# PCB.net
KiCad netlist of a schematic drawn in EAGLE
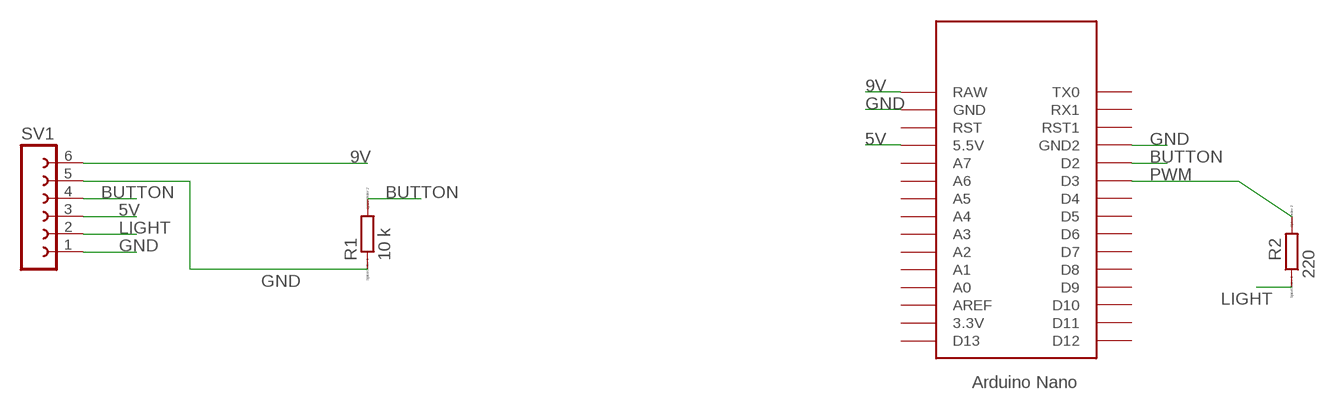
[diagram p0: schematic, sheet 1]

(export (version "E")
  (design (tool "Eeschema 10.0.6"))
  (components
    (comp (ref "R1")
      (value "10 k")
      (footprint "eagle-import:R0805")
      (libsource (lib "eagle-import") (part "R"))
    )
    (comp (ref "R2")
      (value "220")
      (footprint "eagle-import:R0805")
      (libsource (lib "eagle-import") (part "R"))
    )
    (comp (ref "SV1")
      (value "FE06-1")
      (footprint "eagle-import:FE06")
      (libsource (lib "eagle-import") (part "FE06-1"))
    )
    (comp (ref "U$1")
      (value "NANO")
      (footprint "eagle-import:NANO")
      (libsource (lib "eagle-import") (part "NANO"))
    )
  )
  (nets
    (net (code "1") (name "/5V") (class "Default")
      (node (ref "SV1") (pin "3") (pinfunction "3_3") (pintype "passive"))
      (node (ref "U$1") (pin "5V") (pinfunction "5.5V_5V") (pintype "bidirectional"))
    )
    (net (code "2") (name "/9V") (class "Default")
      (node (ref "SV1") (pin "6") (pinfunction "6_6") (pintype "passive"))
      (node (ref "U$1") (pin "RAW") (pinfunction "RAW_RAW") (pintype "bidirectional"))
    )
    (net (code "3") (name "/BUTTON") (class "Default")
      (node (ref "R1") (pin "2") (pinfunction "2_2") (pintype "passive"))
      (node (ref "SV1") (pin "4") (pinfunction "4_4") (pintype "passive"))
      (node (ref "U$1") (pin "D2") (pinfunction "D2_D2") (pintype "bidirectional"))
    )
    (net (code "4") (name "/GND") (class "Default")
      (node (ref "R1") (pin "1") (pinfunction "1_1") (pintype "passive"))
      (node (ref "SV1") (pin "1") (pinfunction "1_1") (pintype "passive"))
      (node (ref "SV1") (pin "5") (pinfunction "5_5") (pintype "passive"))
      (node (ref "U$1") (pin "GND") (pinfunction "GND_GND") (pintype "bidirectional"))
      (node (ref "U$1") (pin "GND1") (pinfunction "GND2_GND1") (pintype "bidirectional"))
    )
    (net (code "5") (name "/LIGHT") (class "Default")
      (node (ref "R2") (pin "1") (pinfunction "1_1") (pintype "passive"))
      (node (ref "SV1") (pin "2") (pinfunction "2_2") (pintype "passive"))
    )
    (net (code "6") (name "/PWM") (class "Default")
      (node (ref "R2") (pin "2") (pinfunction "2_2") (pintype "passive"))
      (node (ref "U$1") (pin "D3") (pinfunction "D3_D3") (pintype "bidirectional"))
    )
    (net (code "7") (name "unconnected-(U$1-Pad3.3V)") (class "Default")
      (node (ref "U$1") (pin "3.3V") (pinfunction "3.3V_3.3V") (pintype "bidirectional"))
    )
    (net (code "8") (name "unconnected-(U$1-PadA0)") (class "Default")
      (node (ref "U$1") (pin "A0") (pinfunction "A0_A0") (pintype "bidirectional"))
    )
    (net (code "9") (name "unconnected-(U$1-PadA1)") (class "Default")
      (node (ref "U$1") (pin "A1") (pinfunction "A1_A1") (pintype "bidirectional"))
    )
    (net (code "10") (name "unconnected-(U$1-PadA2)") (class "Default")
      (node (ref "U$1") (pin "A2") (pinfunction "A2_A2") (pintype "bidirectional"))
    )
    (net (code "11") (name "unconnected-(U$1-PadA3)") (class "Default")
      (node (ref "U$1") (pin "A3") (pinfunction "A3_A3") (pintype "bidirectional"))
    )
    (net (code "12") (name "unconnected-(U$1-PadA4)") (class "Default")
      (node (ref "U$1") (pin "A4") (pinfunction "A4_A4") (pintype "bidirectional"))
    )
    (net (code "13") (name "unconnected-(U$1-PadA5)") (class "Default")
      (node (ref "U$1") (pin "A5") (pinfunction "A5_A5") (pintype "bidirectional"))
    )
    (net (code "14") (name "unconnected-(U$1-PadA6)") (class "Default")
      (node (ref "U$1") (pin "A6") (pinfunction "A6_A6") (pintype "bidirectional"))
    )
    (net (code "15") (name "unconnected-(U$1-PadA7)") (class "Default")
      (node (ref "U$1") (pin "A7") (pinfunction "A7_A7") (pintype "bidirectional"))
    )
    (net (code "16") (name "unconnected-(U$1-PadAREF)") (class "Default")
      (node (ref "U$1") (pin "AREF") (pinfunction "AREF_AREF") (pintype "bidirectional"))
    )
    (net (code "17") (name "unconnected-(U$1-PadD4)") (class "Default")
      (node (ref "U$1") (pin "D4") (pinfunction "D4_D4") (pintype "bidirectional"))
    )
    (net (code "18") (name "unconnected-(U$1-PadD5)") (class "Default")
      (node (ref "U$1") (pin "D5") (pinfunction "D5_D5") (pintype "bidirectional"))
    )
    (net (code "19") (name "unconnected-(U$1-PadD6)") (class "Default")
      (node (ref "U$1") (pin "D6") (pinfunction "D6_D6") (pintype "bidirectional"))
    )
    (net (code "20") (name "unconnected-(U$1-PadD7)") (class "Default")
      (node (ref "U$1") (pin "D7") (pinfunction "D7_D7") (pintype "bidirectional"))
    )
    (net (code "21") (name "unconnected-(U$1-PadD8)") (class "Default")
      (node (ref "U$1") (pin "D8") (pinfunction "D8_D8") (pintype "bidirectional"))
    )
    (net (code "22") (name "unconnected-(U$1-PadD9)") (class "Default")
      (node (ref "U$1") (pin "D9") (pinfunction "D9_D9") (pintype "bidirectional"))
    )
    (net (code "23") (name "unconnected-(U$1-PadD10)") (class "Default")
      (node (ref "U$1") (pin "D10") (pinfunction "D10_D10") (pintype "bidirectional"))
    )
    (net (code "24") (name "unconnected-(U$1-PadD11)") (class "Default")
      (node (ref "U$1") (pin "D11") (pinfunction "D11_D11") (pintype "bidirectional"))
    )
    (net (code "25") (name "unconnected-(U$1-PadD12)") (class "Default")
      (node (ref "U$1") (pin "D12") (pinfunction "D12_D12") (pintype "bidirectional"))
    )
    (net (code "26") (name "unconnected-(U$1-PadD13)") (class "Default")
      (node (ref "U$1") (pin "D13") (pinfunction "D13_D13") (pintype "bidirectional"))
    )
    (net (code "27") (name "unconnected-(U$1-PadICSP1)") (class "Default")
      (node (ref "U$1") (pin "ICSP1") (pinfunction "ICSP1_ICSP1") (pintype "bidirectional"))
    )
    (net (code "28") (name "unconnected-(U$1-PadICSP2)") (class "Default")
      (node (ref "U$1") (pin "ICSP2") (pinfunction "ICSP2_ICSP2") (pintype "bidirectional"))
    )
    (net (code "29") (name "unconnected-(U$1-PadICSP3)") (class "Default")
      (node (ref "U$1") (pin "ICSP3") (pinfunction "ICSP3_ICSP3") (pintype "bidirectional"))
    )
    (net (code "30") (name "unconnected-(U$1-PadICSP4)") (class "Default")
      (node (ref "U$1") (pin "ICSP4") (pinfunction "ICSP4_ICSP4") (pintype "bidirectional"))
    )
    (net (code "31") (name "unconnected-(U$1-PadICSP5)") (class "Default")
      (node (ref "U$1") (pin "ICSP5") (pinfunction "ICSP5_ICSP5") (pintype "bidirectional"))
    )
    (net (code "32") (name "unconnected-(U$1-PadICSP6)") (class "Default")
      (node (ref "U$1") (pin "ICSP6") (pinfunction "ICSP6_ICSP6") (pintype "bidirectional"))
    )
    (net (code "33") (name "unconnected-(U$1-PadRST)") (class "Default")
      (node (ref "U$1") (pin "RST") (pinfunction "RST_RST") (pintype "bidirectional"))
    )
    (net (code "34") (name "unconnected-(U$1-PadRST1)") (class "Default")
      (node (ref "U$1") (pin "RST1") (pinfunction "RST1_RST1") (pintype "bidirectional"))
    )
    (net (code "35") (name "unconnected-(U$1-PadRX1)") (class "Default")
      (node (ref "U$1") (pin "RX1") (pinfunction "RX1_RX1") (pintype "bidirectional"))
    )
    (net (code "36") (name "unconnected-(U$1-PadTX0)") (class "Default")
      (node (ref "U$1") (pin "TX0") (pinfunction "TX0_TX0") (pintype "bidirectional"))
    )
  )
)
